# top.net
KiCad netlist of a schematic drawn in Altium Designer
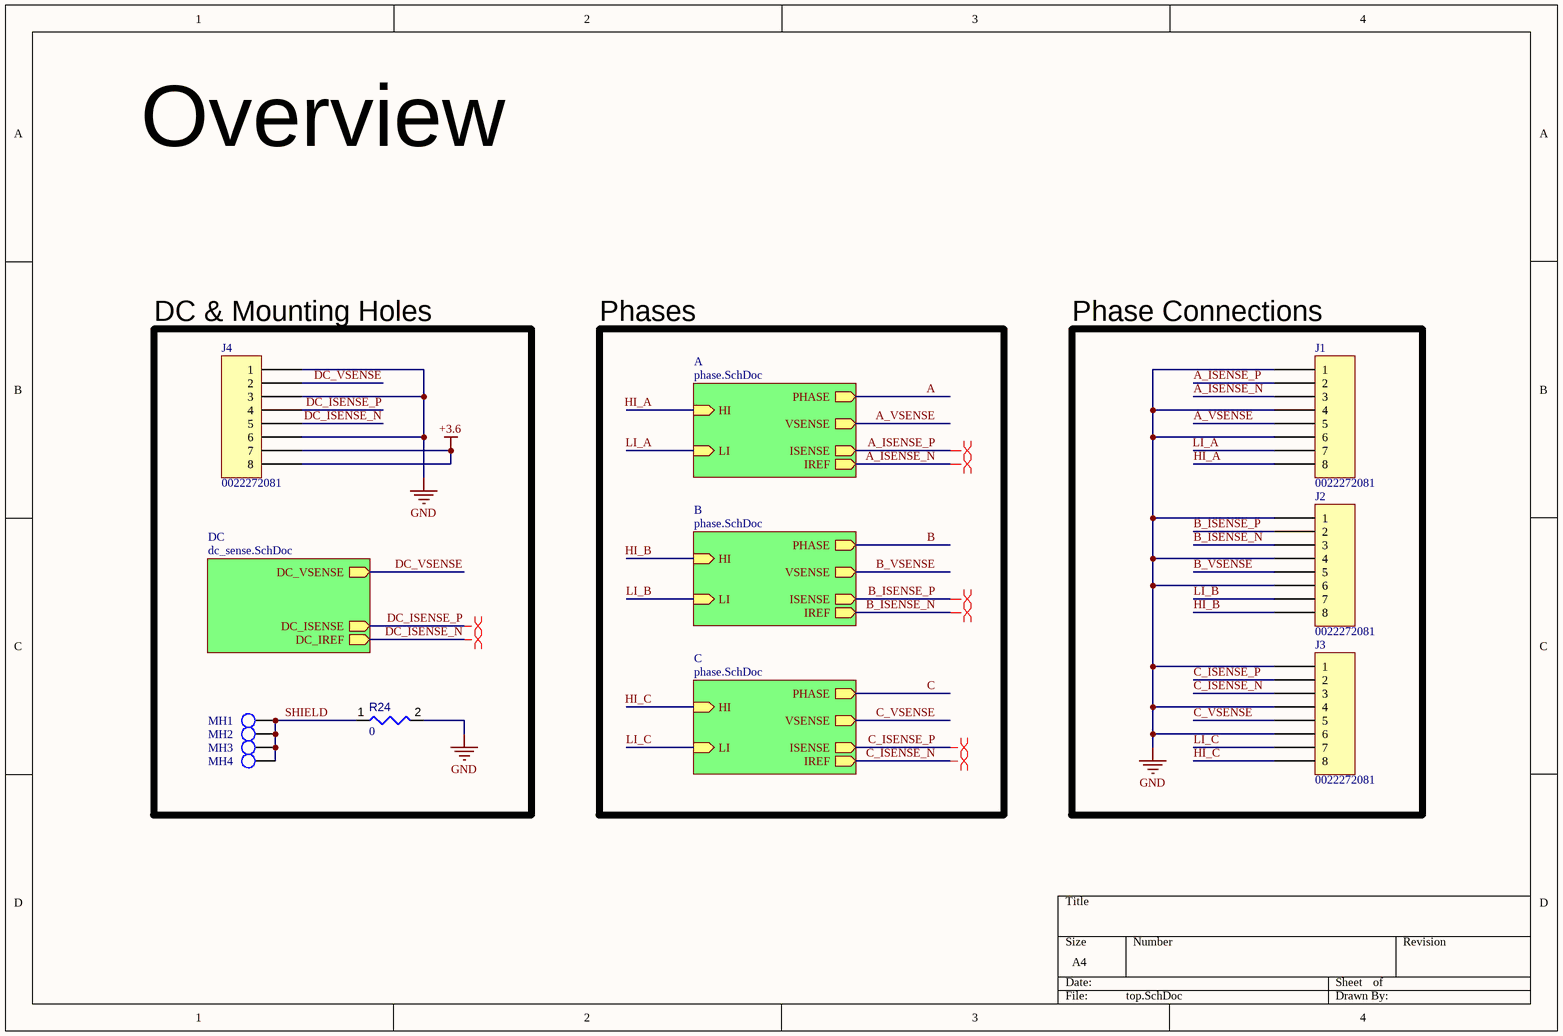
[diagram p0: top.SchDoc]

(export (version "E")
  (design (tool "Eeschema 10.0.6"))
  (components
    (comp (ref "J1")
      (value "0022272081")
      (footprint "MOLEX KK 0022272081")
      (description "CONN HEADER VERT 8POS 2.54MM")
      (fields (field (name "MANUFACTURER") "Molex"))
      (libsource (lib "Americas- Northwestern Formula Racing- Northwestern University") (part "8 PIN"))
    )
    (comp (ref "J2")
      (value "0022272081")
      (footprint "MOLEX KK 0022272081")
      (description "CONN HEADER VERT 8POS 2.54MM")
      (fields (field (name "MANUFACTURER") "Molex"))
      (libsource (lib "Americas- Northwestern Formula Racing- Northwestern University") (part "8 PIN"))
    )
    (comp (ref "J3")
      (value "0022272081")
      (footprint "MOLEX KK 0022272081")
      (description "CONN HEADER VERT 8POS 2.54MM")
      (fields (field (name "MANUFACTURER") "Molex"))
      (libsource (lib "Americas- Northwestern Formula Racing- Northwestern University") (part "8 PIN"))
    )
    (comp (ref "J4")
      (value "0022272081")
      (footprint "MOLEX KK 0022272081")
      (description "CONN HEADER VERT 8POS 2.54MM")
      (fields (field (name "MANUFACTURER") "Molex"))
      (libsource (lib "") (part "8 PIN_1"))
    )
    (comp (ref "MH1")
      (value "Mounting Hole M2.5-Plated")
      (footprint "Copy of Mounting Hole 6-32-Footprint-1")
      (libsource (lib "Americas- Northwestern Formula Racing- Northwestern University") (part "Mounting Hole 6-32-Symbol-1"))
    )
    (comp (ref "MH2")
      (value "Mounting Hole M2.5-Plated")
      (footprint "Copy of Mounting Hole 6-32-Footprint-1")
      (libsource (lib "Americas- Northwestern Formula Racing- Northwestern University") (part "Mounting Hole 6-32-Symbol-1"))
    )
    (comp (ref "MH3")
      (value "Mounting Hole M2.5-Plated")
      (footprint "Copy of Mounting Hole 6-32-Footprint-1")
      (libsource (lib "Americas- Northwestern Formula Racing- Northwestern University") (part "Mounting Hole 6-32-Symbol-1"))
    )
    (comp (ref "MH4")
      (value "Mounting Hole M2.5-Plated")
      (footprint "Copy of Mounting Hole 6-32-Footprint-1")
      (libsource (lib "Americas- Northwestern Formula Racing- Northwestern University") (part "Mounting Hole 6-32-Symbol-1"))
    )
    (comp (ref "R24")
      (value "0")
      (footprint "RESC0603(1608)_L")
      (description "Jumper 0603 (1608 Metric)")
      (fields (field (name "Comment") "0R3J"))
      (libsource (lib "Americas- Northwestern Formula Racing- Northwestern University") (part "0R3J"))
    )
  )
  (nets
    (net (code "1") (name "+3.6") (class "Default")
      (node (ref "J4") (pin "7") (pinfunction "7_7") (pintype "passive"))
      (node (ref "J4") (pin "8") (pinfunction "8_8") (pintype "passive"))
    )
    (net (code "3") (name "/A_ISENSE_N") (class "Default")
      (node (ref "J1") (pin "3") (pinfunction "3_3") (pintype "passive"))
    )
    (net (code "4") (name "/A_ISENSE_P") (class "Default")
      (node (ref "J1") (pin "2") (pinfunction "2_2") (pintype "passive"))
    )
    (net (code "5") (name "/A_VSENSE") (class "Default")
      (node (ref "J1") (pin "5") (pinfunction "5_5") (pintype "passive"))
    )
    (net (code "7") (name "/B_ISENSE_N") (class "Default")
      (node (ref "J2") (pin "3") (pinfunction "3_3") (pintype "passive"))
    )
    (net (code "8") (name "/B_ISENSE_P") (class "Default")
      (node (ref "J2") (pin "2") (pinfunction "2_2") (pintype "passive"))
    )
    (net (code "9") (name "/B_VSENSE") (class "Default")
      (node (ref "J2") (pin "5") (pinfunction "5_5") (pintype "passive"))
    )
    (net (code "11") (name "/C_ISENSE_N") (class "Default")
      (node (ref "J3") (pin "3") (pinfunction "3_3") (pintype "passive"))
    )
    (net (code "12") (name "/C_ISENSE_P") (class "Default")
      (node (ref "J3") (pin "2") (pinfunction "2_2") (pintype "passive"))
    )
    (net (code "13") (name "/C_VSENSE") (class "Default")
      (node (ref "J3") (pin "5") (pinfunction "5_5") (pintype "passive"))
    )
    (net (code "14") (name "/DC_ISENSE_N") (class "Default")
      (node (ref "J4") (pin "5") (pinfunction "5_5") (pintype "passive"))
    )
    (net (code "15") (name "/DC_ISENSE_P") (class "Default")
      (node (ref "J4") (pin "4") (pinfunction "4_4") (pintype "passive"))
    )
    (net (code "16") (name "/DC_VSENSE") (class "Default")
      (node (ref "J4") (pin "2") (pinfunction "2_2") (pintype "passive"))
    )
    (net (code "17") (name "/HI_A") (class "Default")
      (node (ref "J1") (pin "8") (pinfunction "8_8") (pintype "passive"))
    )
    (net (code "18") (name "/HI_B") (class "Default")
      (node (ref "J2") (pin "8") (pinfunction "8_8") (pintype "passive"))
    )
    (net (code "19") (name "/HI_C") (class "Default")
      (node (ref "J3") (pin "8") (pinfunction "8_8") (pintype "passive"))
    )
    (net (code "20") (name "/LI_A") (class "Default")
      (node (ref "J1") (pin "7") (pinfunction "7_7") (pintype "passive"))
    )
    (net (code "21") (name "/LI_B") (class "Default")
      (node (ref "J2") (pin "7") (pinfunction "7_7") (pintype "passive"))
    )
    (net (code "22") (name "/LI_C") (class "Default")
      (node (ref "J3") (pin "7") (pinfunction "7_7") (pintype "passive"))
    )
    (net (code "23") (name "/SHIELD") (class "Default")
      (node (ref "MH1") (pin "1") (pinfunction "1_1") (pintype "passive"))
      (node (ref "MH2") (pin "1") (pinfunction "1_1") (pintype "passive"))
      (node (ref "MH3") (pin "1") (pinfunction "1_1") (pintype "passive"))
      (node (ref "MH4") (pin "1") (pinfunction "1_1") (pintype "passive"))
      (node (ref "R24") (pin "1") (pinfunction "1_1") (pintype "passive"))
    )
    (net (code "24") (name "GND") (class "Default")
      (node (ref "J1") (pin "1") (pinfunction "1_1") (pintype "passive"))
      (node (ref "J1") (pin "4") (pinfunction "4_4") (pintype "passive"))
      (node (ref "J1") (pin "6") (pinfunction "6_6") (pintype "passive"))
      (node (ref "J2") (pin "1") (pinfunction "1_1") (pintype "passive"))
      (node (ref "J2") (pin "4") (pinfunction "4_4") (pintype "passive"))
      (node (ref "J2") (pin "6") (pinfunction "6_6") (pintype "passive"))
      (node (ref "J3") (pin "1") (pinfunction "1_1") (pintype "passive"))
      (node (ref "J3") (pin "4") (pinfunction "4_4") (pintype "passive"))
      (node (ref "J3") (pin "6") (pinfunction "6_6") (pintype "passive"))
      (node (ref "J4") (pin "1") (pinfunction "1_1") (pintype "passive"))
      (node (ref "J4") (pin "3") (pinfunction "3_3") (pintype "passive"))
      (node (ref "J4") (pin "6") (pinfunction "6_6") (pintype "passive"))
      (node (ref "R24") (pin "2") (pinfunction "2_2") (pintype "passive"))
    )
  )
)
